# Power.net
KiCad netlist of a schematic drawn in Altium Designer
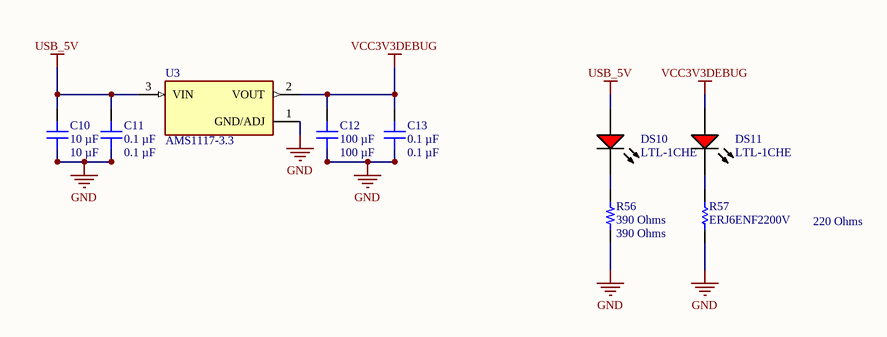
[diagram p0: Power.SchDoc]

(export (version "E")
  (design (tool "Eeschema 10.0.6"))
  (components
    (comp (ref "C10")
      (value "10 µF")
      (footprint "CAP 0805_2012")
      (description "CAP CER 10UF 10V X7S 0805")
      (fields (field (name "PART NUMBER") "CL21Y106KPQVPNE") (field (name "ALTIUM_VALUE") "10 µF"))
      (libsource (lib "Celestial Altium Library - altium_library") (part "Capacitor"))
    )
    (comp (ref "C11")
      (value "0.1 µF")
      (footprint "CAP 0805_2012")
      (description "CAP CER 0.1UF 50V X7R 0805")
      (fields (field (name "PART NUMBER") "CC0805MRX7R9BB104") (field (name "ALTIUM_VALUE") "0.1 µF"))
      (libsource (lib "Celestial Altium Library - altium_library") (part "Capacitor"))
    )
    (comp (ref "C12")
      (value "100 µF")
      (footprint "CAP 0805_2012")
      (description "CAP CER 100UF 2.5V X5R 0805")
      (fields (field (name "PART NUMBER") "PMK212BBJ107MG-T") (field (name "ALTIUM_VALUE") "100 µF"))
      (libsource (lib "Celestial Altium Library - altium_library") (part "Capacitor"))
    )
    (comp (ref "C13")
      (value "0.1 µF")
      (footprint "CAP 0805_2012")
      (description "CAP CER 0.1UF 50V X7R 0805")
      (fields (field (name "PART NUMBER") "CC0805MRX7R9BB104") (field (name "ALTIUM_VALUE") "0.1 µF"))
      (libsource (lib "Celestial Altium Library - altium_library") (part "Capacitor"))
    )
    (comp (ref "DS10")
      (value "LTL-1CHE")
      (footprint "INDPR60-254-520X380X650")
      (description "Radial LED, 12.6 mcd, 20 mA, 2 V, -55 to 100 degC, 2-Pin THD, RoHS, Bulk")
      (fields (field (name "TOLERANCE") "20%"))
      (libsource (lib "Altium Content Vault") (part "LED-RED-AK-2"))
    )
    (comp (ref "DS11")
      (value "LTL-1CHE")
      (footprint "INDPR60-254-520X380X650")
      (description "Radial LED, 12.6 mcd, 20 mA, 2 V, -55 to 100 degC, 2-Pin THD, RoHS, Bulk")
      (fields (field (name "TOLERANCE") "20%"))
      (libsource (lib "Altium Content Vault") (part "LED-RED-AK-2"))
    )
    (comp (ref "R56")
      (value "390 Ohms")
      (footprint "RES 0805_2012")
      (description "RES 390 OHM 1% 1/3W 0805")
      (fields (field (name "PART NUMBER") "CRGP0805F390R") (field (name "ALTIUM_VALUE") "390 Ohms"))
      (libsource (lib "Celestial Altium Library - altium_library") (part "Resistor"))
    )
    (comp (ref "R57")
      (value "ERJ6ENF2200V")
      (footprint "RESC2013X70X40NL20T20")
      (fields (field (name "MANUFACTURER") "Panasonic"))
      (libsource (lib "Altium Content Vault") (part "RES"))
    )
    (comp (ref "U3")
      (value "AMS1117-3.3")
      (footprint "SOT229P700X180-4N")
      (description "Sot223/Pkg 1-Amp 3.3-Volt Low Drop Out Voltage Regulatator")
      (fields (field (name "MF") "Advanced Monolithic Systems"))
      (libsource (lib "AMS1117-3.3") (part "AMS1117-3.3"))
    )
  )
  (nets
    (net (code "1") (name "GND") (class "Default")
      (node (ref "C10") (pin "1") (pinfunction "1_1") (pintype "passive"))
      (node (ref "C11") (pin "1") (pinfunction "1_1") (pintype "passive"))
      (node (ref "C12") (pin "1") (pinfunction "1_1") (pintype "passive"))
      (node (ref "C13") (pin "1") (pinfunction "1_1") (pintype "passive"))
      (node (ref "R56") (pin "1") (pinfunction "1_1") (pintype "passive"))
      (node (ref "R57") (pin "1") (pinfunction "1_1") (pintype "passive"))
      (node (ref "U3") (pin "1") (pinfunction "GND/ADJ_1") (pintype "power_in"))
    )
    (net (code "2") (name "Net-(DS10-K)") (class "Default")
      (node (ref "DS10") (pin "2") (pinfunction "K_2") (pintype "passive"))
      (node (ref "R56") (pin "2") (pinfunction "2_2") (pintype "passive"))
    )
    (net (code "3") (name "Net-(DS11-K)") (class "Default")
      (node (ref "DS11") (pin "2") (pinfunction "K_2") (pintype "passive"))
      (node (ref "R57") (pin "2") (pinfunction "2_2") (pintype "passive"))
    )
    (net (code "4") (name "USB_5V") (class "Default")
      (node (ref "C10") (pin "2") (pinfunction "2_2") (pintype "passive"))
      (node (ref "C11") (pin "2") (pinfunction "2_2") (pintype "passive"))
      (node (ref "DS10") (pin "1") (pinfunction "A_1") (pintype "passive"))
      (node (ref "U3") (pin "3") (pinfunction "VIN_3") (pintype "input"))
    )
    (net (code "5") (name "VCC3V3DEBUG") (class "Default")
      (node (ref "C12") (pin "2") (pinfunction "2_2") (pintype "passive"))
      (node (ref "C13") (pin "2") (pinfunction "2_2") (pintype "passive"))
      (node (ref "DS11") (pin "1") (pinfunction "A_1") (pintype "passive"))
      (node (ref "U3") (pin "2") (pinfunction "VOUT_2") (pintype "output"))
    )
  )
)
